# i2cstump-usbc.net
KiCad netlist of a schematic drawn in EAGLE
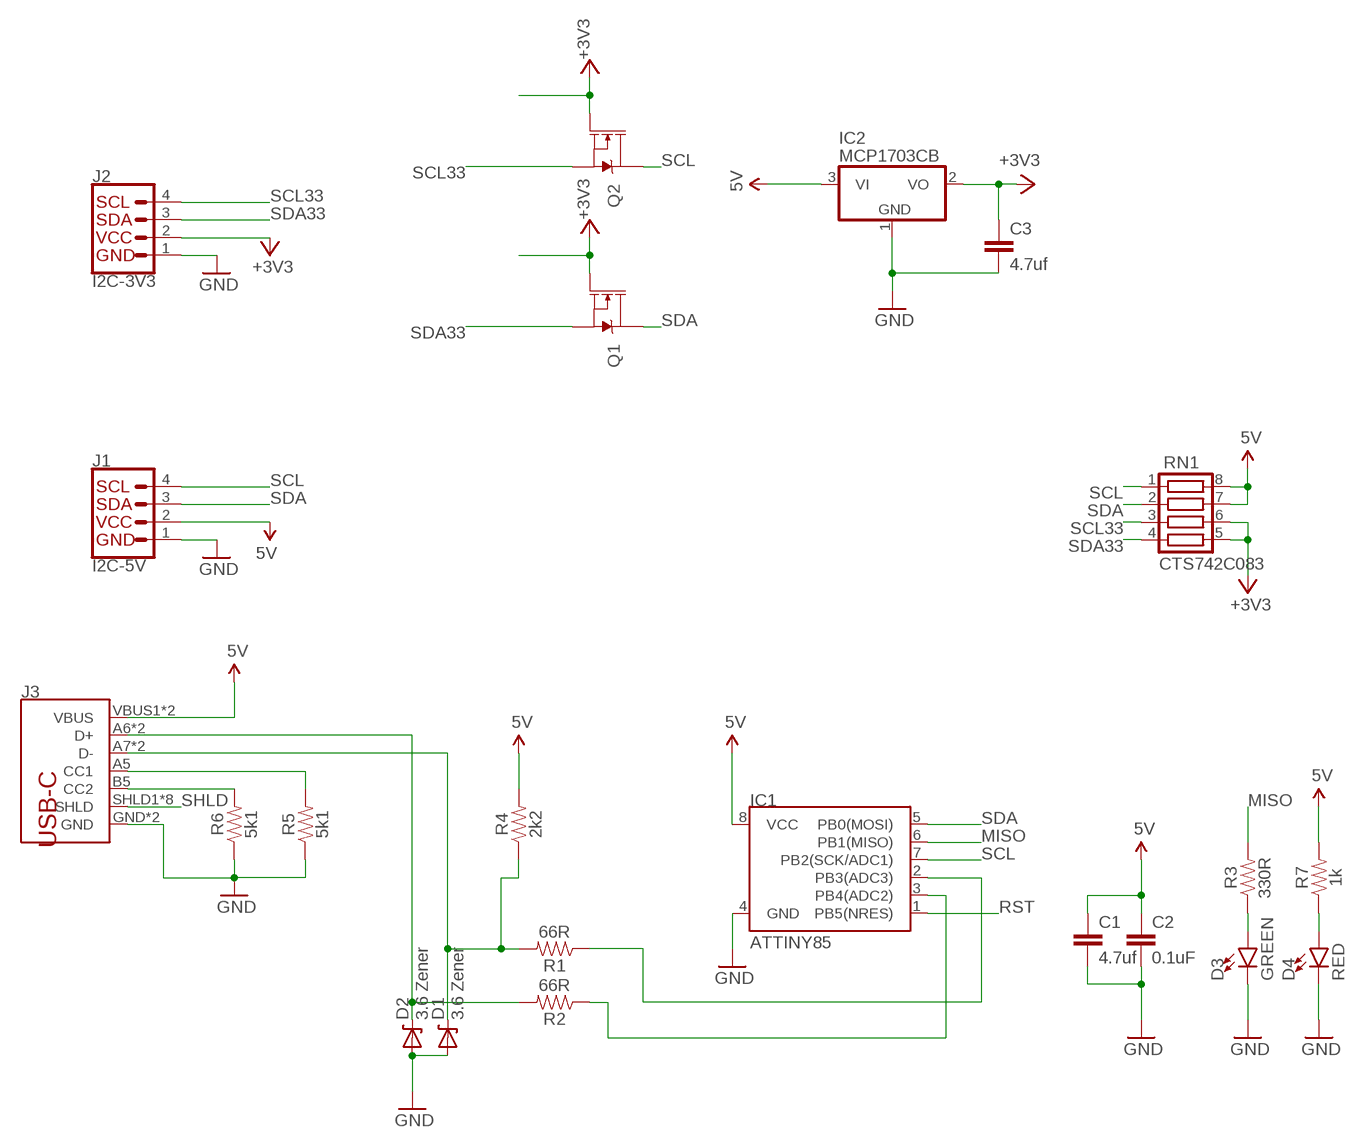
[diagram p0: schematic, sheet 1]

(export (version "E")
  (design (tool "Eeschema 10.0.6"))
  (components
    (comp (ref "C1")
      (value "4.7uf")
      (footprint "eagle-import:0805")
      (libsource (lib "eagle-import") (part "CAP0805"))
    )
    (comp (ref "C2")
      (value "0.1uF")
      (footprint "eagle-import:0603")
      (libsource (lib "eagle-import") (part "0.1UF-0603-25V-(+80/-20%)"))
    )
    (comp (ref "C3")
      (value "4.7uf")
      (footprint "eagle-import:0805")
      (libsource (lib "eagle-import") (part "CAP0805"))
    )
    (comp (ref "D1")
      (value "3.6 Zener")
      (footprint "eagle-import:SOD-323")
      (libsource (lib "eagle-import") (part "DIODE-ZENER-BZT52"))
    )
    (comp (ref "D2")
      (value "3.6 Zener")
      (footprint "eagle-import:SOD-323")
      (libsource (lib "eagle-import") (part "DIODE-ZENER-BZT52"))
    )
    (comp (ref "D3")
      (value "GREEN")
      (footprint "eagle-import:LED-0603")
      (libsource (lib "eagle-import") (part "LED-GREEN0603"))
    )
    (comp (ref "D4")
      (value "RED")
      (footprint "eagle-import:LED-0603")
      (libsource (lib "eagle-import") (part "LED-GREEN0603"))
    )
    (comp (ref "IC1")
      (value "ATTINY85")
      (footprint "eagle-import:SO08-EIAJ")
      (libsource (lib "eagle-import") (part "ATTINY45"))
    )
    (comp (ref "IC2")
      (value "MCP1703CB")
      (footprint "eagle-import:SOT23")
      (libsource (lib "eagle-import") (part "MCP1703CB"))
    )
    (comp (ref "J1")
      (value "I2C-5V")
      (footprint "eagle-import:1X04_1MM_RA")
      (libsource (lib "eagle-import") (part "QWIIC_CONNECTORJS-1MM"))
    )
    (comp (ref "J2")
      (value "I2C-3V3")
      (footprint "eagle-import:1X04_1MM_RA")
      (libsource (lib "eagle-import") (part "QWIIC_CONNECTORJS-1MM"))
    )
    (comp (ref "J3")
      (value "USB_C16PIN")
      (footprint "eagle-import:USB-C-16P")
      (libsource (lib "eagle-import") (part "USB_C16PIN"))
    )
    (comp (ref "Q1")
      (value "220mA/50V/3.5Ω")
      (footprint "eagle-import:SOT23-3")
      (libsource (lib "eagle-import") (part "MOSFET-NCH-BSS138"))
    )
    (comp (ref "Q2")
      (value "220mA/50V/3.5Ω")
      (footprint "eagle-import:SOT23-3")
      (libsource (lib "eagle-import") (part "MOSFET-NCH-BSS138"))
    )
    (comp (ref "R1")
      (value "66R")
      (footprint "eagle-import:0603")
      (libsource (lib "eagle-import") (part "RESISTOR0603"))
    )
    (comp (ref "R2")
      (value "66R")
      (footprint "eagle-import:0603")
      (libsource (lib "eagle-import") (part "RESISTOR0603"))
    )
    (comp (ref "R3")
      (value "330R")
      (footprint "eagle-import:0603")
      (libsource (lib "eagle-import") (part "RESISTOR0603"))
    )
    (comp (ref "R4")
      (value "2k2")
      (footprint "eagle-import:0603")
      (libsource (lib "eagle-import") (part "RESISTOR0603"))
    )
    (comp (ref "R5")
      (value "5k1")
      (footprint "eagle-import:0603")
      (libsource (lib "eagle-import") (part "RESISTOR0603"))
    )
    (comp (ref "R6")
      (value "5k1")
      (footprint "eagle-import:0603")
      (libsource (lib "eagle-import") (part "RESISTOR0603"))
    )
    (comp (ref "R7")
      (value "1k")
      (footprint "eagle-import:0603")
      (libsource (lib "eagle-import") (part "RESISTOR0603"))
    )
    (comp (ref "RN1")
      (value "CTS742C083")
      (footprint "eagle-import:CTS742C083")
      (libsource (lib "eagle-import") (part "CTS742C083"))
    )
  )
  (nets
    (net (code "1") (name "+3V3") (class "Default")
      (node (ref "C3") (pin "1") (pinfunction "1_1") (pintype "passive"))
      (node (ref "IC2") (pin "2") (pinfunction "VO_2") (pintype "passive"))
      (node (ref "J2") (pin "2") (pinfunction "VCC_2") (pintype "power_in"))
      (node (ref "Q1") (pin "1") (pinfunction "G_1") (pintype "bidirectional"))
      (node (ref "Q2") (pin "1") (pinfunction "G_1") (pintype "bidirectional"))
      (node (ref "RN1") (pin "5") (pinfunction "5_5") (pintype "passive"))
      (node (ref "RN1") (pin "6") (pinfunction "6_6") (pintype "passive"))
    )
    (net (code "2") (name "/MISO") (class "Default")
      (node (ref "IC1") (pin "6") (pinfunction "PB1(MISO)_6") (pintype "bidirectional"))
      (node (ref "R3") (pin "2") (pinfunction "2_2") (pintype "passive"))
    )
    (net (code "3") (name "/RST") (class "Default")
      (node (ref "IC1") (pin "1") (pinfunction "PB5(NRES)_1") (pintype "bidirectional"))
    )
    (net (code "4") (name "/SCL") (class "Default")
      (node (ref "IC1") (pin "7") (pinfunction "PB2(SCK/ADC1)_7") (pintype "bidirectional"))
      (node (ref "J1") (pin "4") (pinfunction "SCL_4") (pintype "passive"))
      (node (ref "Q2") (pin "3") (pinfunction "D_3") (pintype "bidirectional"))
      (node (ref "RN1") (pin "1") (pinfunction "1_1") (pintype "passive"))
    )
    (net (code "5") (name "/SCL33") (class "Default")
      (node (ref "J2") (pin "4") (pinfunction "SCL_4") (pintype "passive"))
      (node (ref "Q2") (pin "2") (pinfunction "S_2") (pintype "bidirectional"))
      (node (ref "RN1") (pin "3") (pinfunction "3_3") (pintype "passive"))
    )
    (net (code "6") (name "/SDA") (class "Default")
      (node (ref "IC1") (pin "5") (pinfunction "PB0(MOSI)_5") (pintype "bidirectional"))
      (node (ref "J1") (pin "3") (pinfunction "SDA_3") (pintype "passive"))
      (node (ref "Q1") (pin "3") (pinfunction "D_3") (pintype "bidirectional"))
      (node (ref "RN1") (pin "2") (pinfunction "2_2") (pintype "passive"))
    )
    (net (code "7") (name "/SDA33") (class "Default")
      (node (ref "J2") (pin "3") (pinfunction "SDA_3") (pintype "passive"))
      (node (ref "Q1") (pin "2") (pinfunction "S_2") (pintype "bidirectional"))
      (node (ref "RN1") (pin "4") (pinfunction "4_4") (pintype "passive"))
    )
    (net (code "8") (name "/SHLD") (class "Default")
      (node (ref "J3") (pin "SHLD1") (pinfunction "SHLD_SHLD1") (pintype "bidirectional"))
      (node (ref "J3") (pin "SHLD2") (pinfunction "SHLD_SHLD2") (pintype "bidirectional"))
      (node (ref "J3") (pin "SHLD3") (pinfunction "SHLD_SHLD3") (pintype "bidirectional"))
      (node (ref "J3") (pin "SHLD4") (pinfunction "SHLD_SHLD4") (pintype "bidirectional"))
      (node (ref "J3") (pin "SHLD5") (pinfunction "SHLD_SHLD5") (pintype "bidirectional"))
      (node (ref "J3") (pin "SHLD6") (pinfunction "SHLD_SHLD6") (pintype "bidirectional"))
      (node (ref "J3") (pin "SHLD7") (pinfunction "SHLD_SHLD7") (pintype "bidirectional"))
      (node (ref "J3") (pin "SHLD8") (pinfunction "SHLD_SHLD8") (pintype "bidirectional"))
    )
    (net (code "9") (name "5V") (class "Default")
      (node (ref "C1") (pin "1") (pinfunction "1_1") (pintype "passive"))
      (node (ref "C2") (pin "1") (pinfunction "1_1") (pintype "passive"))
      (node (ref "IC1") (pin "8") (pinfunction "VCC_8") (pintype "bidirectional"))
      (node (ref "IC2") (pin "3") (pinfunction "VI_3") (pintype "input"))
      (node (ref "J1") (pin "2") (pinfunction "VCC_2") (pintype "power_in"))
      (node (ref "J3") (pin "VBUS1") (pinfunction "VBUS_VBUS1") (pintype "bidirectional"))
      (node (ref "J3") (pin "VBUS2") (pinfunction "VBUS_VBUS2") (pintype "bidirectional"))
      (node (ref "R4") (pin "2") (pinfunction "2_2") (pintype "passive"))
      (node (ref "R7") (pin "2") (pinfunction "2_2") (pintype "passive"))
      (node (ref "RN1") (pin "7") (pinfunction "7_7") (pintype "passive"))
      (node (ref "RN1") (pin "8") (pinfunction "8_8") (pintype "passive"))
    )
    (net (code "10") (name "GND") (class "Default")
      (node (ref "C1") (pin "2") (pinfunction "2_2") (pintype "passive"))
      (node (ref "C2") (pin "2") (pinfunction "2_2") (pintype "passive"))
      (node (ref "C3") (pin "2") (pinfunction "2_2") (pintype "passive"))
      (node (ref "D1") (pin "2") (pinfunction "A_2") (pintype "passive"))
      (node (ref "D2") (pin "2") (pinfunction "A_2") (pintype "passive"))
      (node (ref "D3") (pin "C") (pinfunction "C_C") (pintype "passive"))
      (node (ref "D4") (pin "C") (pinfunction "C_C") (pintype "passive"))
      (node (ref "IC1") (pin "4") (pinfunction "GND_4") (pintype "bidirectional"))
      (node (ref "IC2") (pin "1") (pinfunction "GND_1") (pintype "passive"))
      (node (ref "J1") (pin "1") (pinfunction "GND_1") (pintype "power_in"))
      (node (ref "J2") (pin "1") (pinfunction "GND_1") (pintype "power_in"))
      (node (ref "J3") (pin "GND") (pinfunction "GND_GND") (pintype "bidirectional"))
      (node (ref "J3") (pin "GND2") (pinfunction "GND_GND2") (pintype "bidirectional"))
      (node (ref "R5") (pin "1") (pinfunction "1_1") (pintype "passive"))
      (node (ref "R6") (pin "1") (pinfunction "1_1") (pintype "passive"))
    )
    (net (code "11") (name "Net-(D1-C)") (class "Default")
      (node (ref "D1") (pin "1") (pinfunction "C_1") (pintype "passive"))
      (node (ref "J3") (pin "A7") (pinfunction "D-_A7") (pintype "bidirectional"))
      (node (ref "J3") (pin "B7") (pinfunction "D-_B7") (pintype "bidirectional"))
      (node (ref "R1") (pin "2") (pinfunction "2_2") (pintype "passive"))
      (node (ref "R4") (pin "1") (pinfunction "1_1") (pintype "passive"))
    )
    (net (code "12") (name "Net-(D2-C)") (class "Default")
      (node (ref "D2") (pin "1") (pinfunction "C_1") (pintype "passive"))
      (node (ref "J3") (pin "A6") (pinfunction "D+_A6") (pintype "bidirectional"))
      (node (ref "J3") (pin "B6") (pinfunction "D+_B6") (pintype "bidirectional"))
      (node (ref "R2") (pin "2") (pinfunction "2_2") (pintype "passive"))
    )
    (net (code "13") (name "Net-(D3-PadA)") (class "Default")
      (node (ref "D3") (pin "A") (pinfunction "A_A") (pintype "passive"))
      (node (ref "R3") (pin "1") (pinfunction "1_1") (pintype "passive"))
    )
    (net (code "14") (name "Net-(D4-PadA)") (class "Default")
      (node (ref "D4") (pin "A") (pinfunction "A_A") (pintype "passive"))
      (node (ref "R7") (pin "1") (pinfunction "1_1") (pintype "passive"))
    )
    (net (code "15") (name "Net-(IC1-PB3(ADC3))") (class "Default")
      (node (ref "IC1") (pin "2") (pinfunction "PB3(ADC3)_2") (pintype "bidirectional"))
      (node (ref "R1") (pin "1") (pinfunction "1_1") (pintype "passive"))
    )
    (net (code "16") (name "Net-(IC1-PB4(ADC2))") (class "Default")
      (node (ref "IC1") (pin "3") (pinfunction "PB4(ADC2)_3") (pintype "bidirectional"))
      (node (ref "R2") (pin "1") (pinfunction "1_1") (pintype "passive"))
    )
    (net (code "17") (name "Net-(J3-CC1)") (class "Default")
      (node (ref "J3") (pin "A5") (pinfunction "CC1_A5") (pintype "bidirectional"))
      (node (ref "R5") (pin "2") (pinfunction "2_2") (pintype "passive"))
    )
    (net (code "18") (name "Net-(J3-CC2)") (class "Default")
      (node (ref "J3") (pin "B5") (pinfunction "CC2_B5") (pintype "bidirectional"))
      (node (ref "R6") (pin "2") (pinfunction "2_2") (pintype "passive"))
    )
  )
)
